# ArduinoShield101.net
KiCad netlist of a schematic drawn in EAGLE
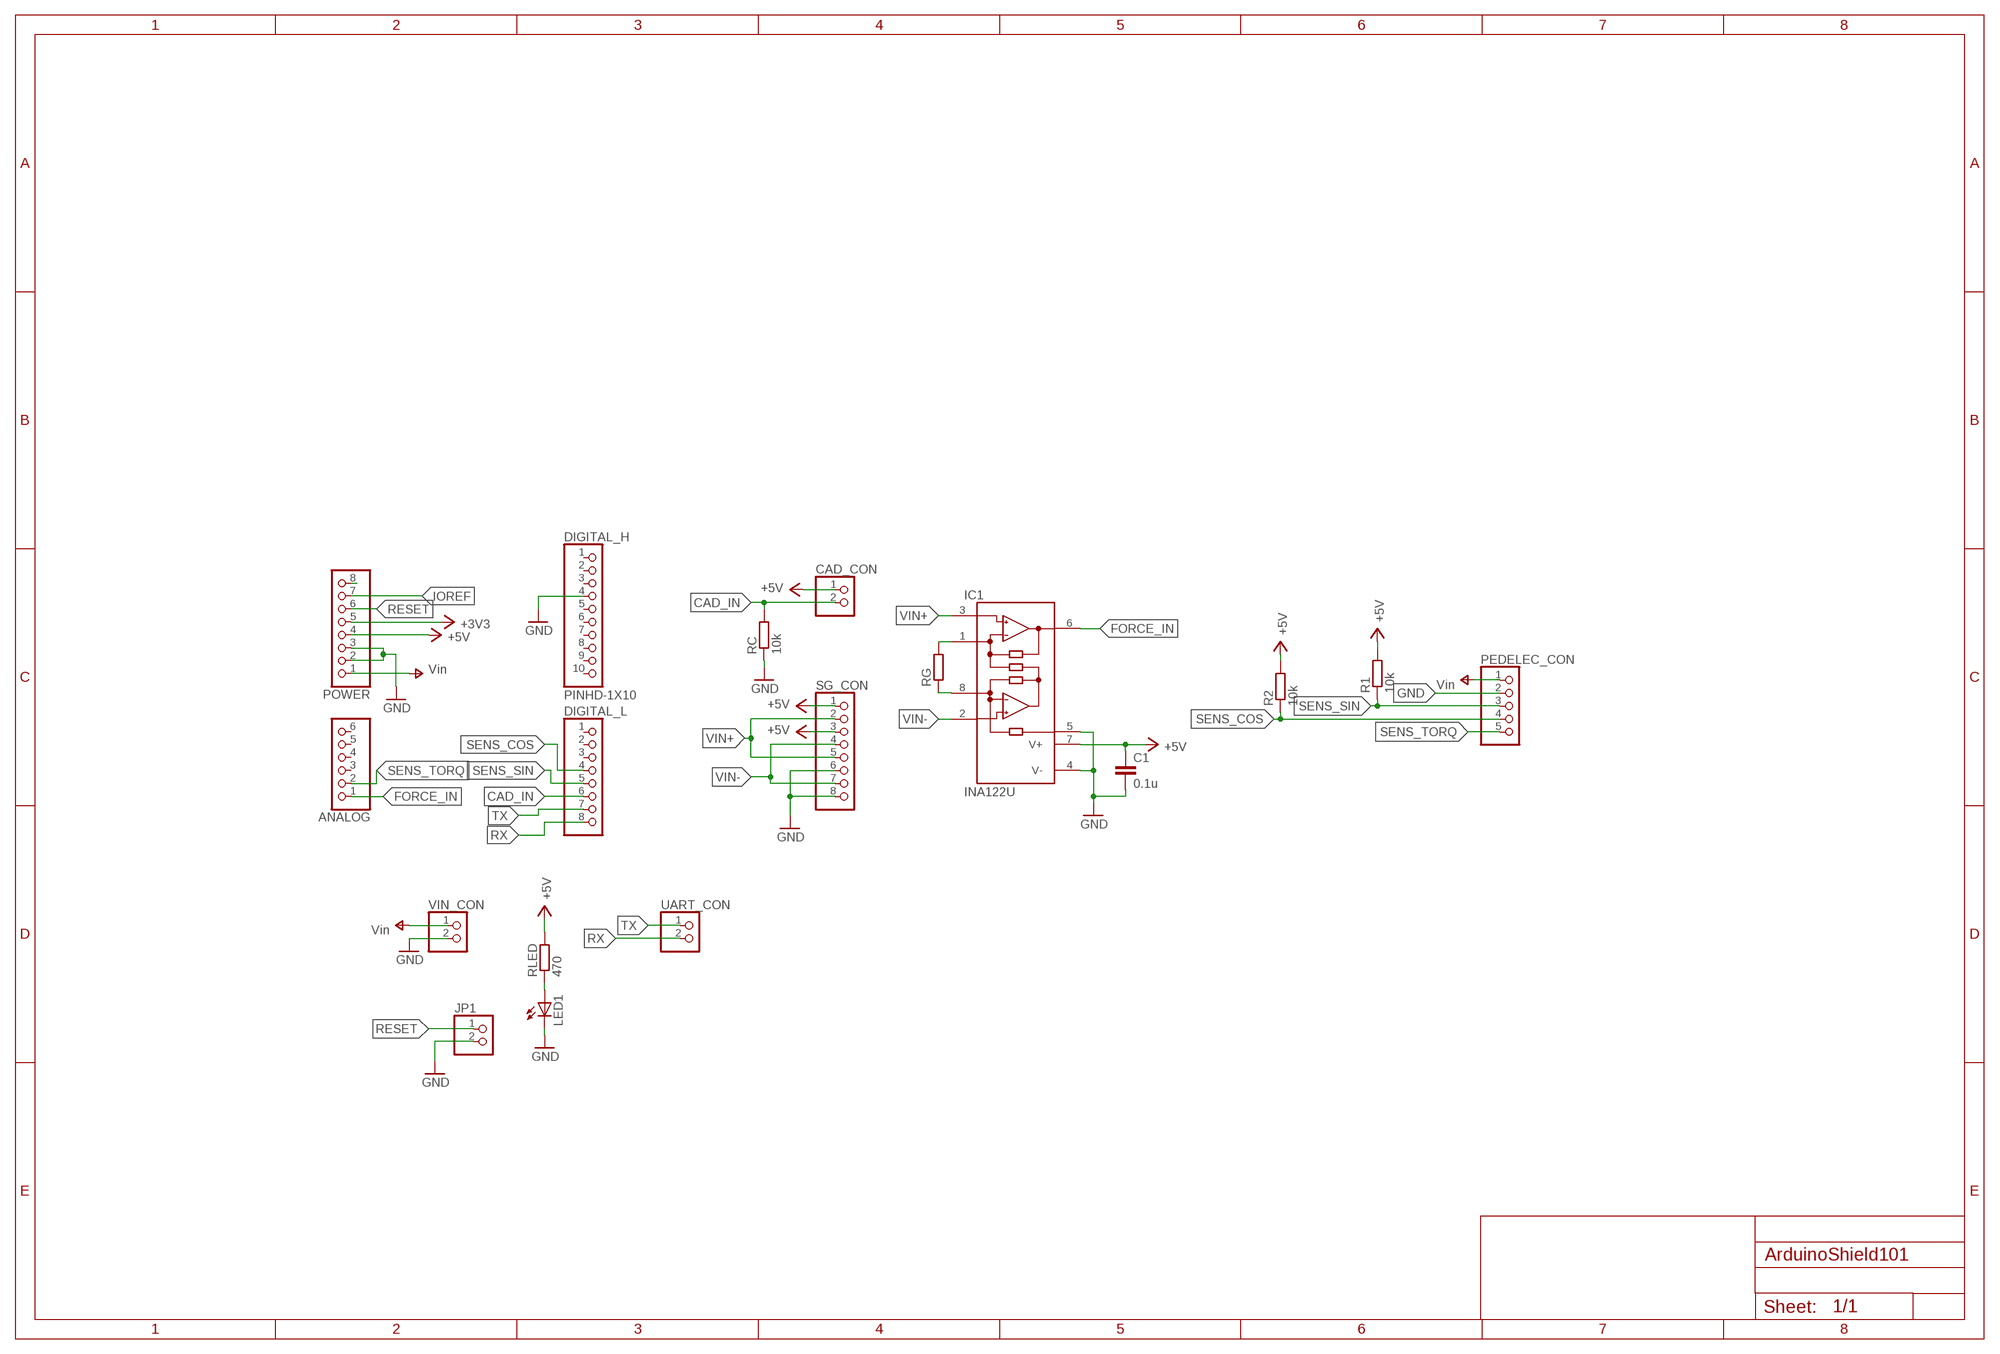
[diagram p0: schematic, sheet 1]

(export (version "E")
  (design (tool "Eeschema 10.0.6"))
  (components
    (comp (ref "ANALOG")
      (value "PINHD-1X6B")
      (footprint "eagle-import:1X06-BIG")
      (libsource (lib "eagle-import") (part "PINHD-1X6B"))
    )
    (comp (ref "C1")
      (value "0.1u")
      (footprint "eagle-import:C0603")
      (libsource (lib "eagle-import") (part "C-EUC0603"))
    )
    (comp (ref "CAD_CON")
      (value "PINHD-1X2/90")
      (footprint "eagle-import:1X02_90")
      (libsource (lib "eagle-import") (part "PINHD-1X2/90"))
    )
    (comp (ref "DIGITAL_H")
      (value "PINHD-1X10")
      (footprint "eagle-import:1X10-BIG")
      (libsource (lib "eagle-import") (part "PINHD-1X10"))
    )
    (comp (ref "DIGITAL_L")
      (value "PINHD-1X8BIG")
      (footprint "eagle-import:1X08-BIG")
      (libsource (lib "eagle-import") (part "PINHD-1X8BIG"))
    )
    (comp (ref "IC1")
      (value "INA122U")
      (footprint "eagle-import:SO08")
      (libsource (lib "eagle-import") (part "INA122U"))
    )
    (comp (ref "JP1")
      (value "PINHD-1X2")
      (footprint "eagle-import:1X02")
      (libsource (lib "eagle-import") (part "PINHD-1X2"))
    )
    (comp (ref "LED1")
      (value "LEDCHIPLED_0603")
      (footprint "eagle-import:CHIPLED_0603")
      (libsource (lib "eagle-import") (part "LEDCHIPLED_0603"))
    )
    (comp (ref "PEDELEC_CON")
      (value "PINHD-1X5/90")
      (footprint "eagle-import:1X05_90")
      (libsource (lib "eagle-import") (part "PINHD-1X5/90"))
    )
    (comp (ref "POWER")
      (value "PINHD-1X8BIG")
      (footprint "eagle-import:1X08-BIG")
      (libsource (lib "eagle-import") (part "PINHD-1X8BIG"))
    )
    (comp (ref "R1")
      (value "10k")
      (footprint "eagle-import:R0603")
      (libsource (lib "eagle-import") (part "R-EU_R0603"))
    )
    (comp (ref "R2")
      (value "10k")
      (footprint "eagle-import:R0603")
      (libsource (lib "eagle-import") (part "R-EU_R0603"))
    )
    (comp (ref "RC")
      (value "10k")
      (footprint "eagle-import:R0603")
      (libsource (lib "eagle-import") (part "R-EU_R0603"))
    )
    (comp (ref "RG")
      (value "R-EU_R0603")
      (footprint "eagle-import:R0603")
      (libsource (lib "eagle-import") (part "R-EU_R0603"))
    )
    (comp (ref "RLED")
      (value "470")
      (footprint "eagle-import:R0603")
      (libsource (lib "eagle-import") (part "R-EU_R0603"))
    )
    (comp (ref "SG_CON")
      (value "PINHD-1X8/90")
      (footprint "eagle-import:1X08_90")
      (libsource (lib "eagle-import") (part "PINHD-1X8/90"))
    )
    (comp (ref "UART_CON")
      (value "PINHD-1X2/90")
      (footprint "eagle-import:1X02_90")
      (libsource (lib "eagle-import") (part "PINHD-1X2/90"))
    )
    (comp (ref "VIN_CON")
      (value "PINHD-1X2/90")
      (footprint "eagle-import:1X02_90")
      (libsource (lib "eagle-import") (part "PINHD-1X2/90"))
    )
  )
  (nets
    (net (code "1") (name "+3V3") (class "Default")
      (node (ref "POWER") (pin "5") (pinfunction "5_5") (pintype "passive"))
    )
    (net (code "2") (name "+5V") (class "Default")
      (node (ref "C1") (pin "1") (pinfunction "1_1") (pintype "passive"))
      (node (ref "CAD_CON") (pin "1") (pinfunction "1_1") (pintype "passive"))
      (node (ref "IC1") (pin "7") (pinfunction "V+_7") (pintype "power_in"))
      (node (ref "POWER") (pin "4") (pinfunction "4_4") (pintype "passive"))
      (node (ref "R1") (pin "2") (pinfunction "2_2") (pintype "passive"))
      (node (ref "R2") (pin "2") (pinfunction "2_2") (pintype "passive"))
      (node (ref "RLED") (pin "2") (pinfunction "2_2") (pintype "passive"))
      (node (ref "SG_CON") (pin "1") (pinfunction "1_1") (pintype "passive"))
      (node (ref "SG_CON") (pin "3") (pinfunction "3_3") (pintype "passive"))
    )
    (net (code "3") (name "CAD_IN") (class "Default")
      (node (ref "CAD_CON") (pin "2") (pinfunction "2_2") (pintype "passive"))
      (node (ref "DIGITAL_L") (pin "6") (pinfunction "6_6") (pintype "passive"))
      (node (ref "RC") (pin "2") (pinfunction "2_2") (pintype "passive"))
    )
    (net (code "4") (name "FORCE_IN") (class "Default")
      (node (ref "ANALOG") (pin "1") (pinfunction "1_1") (pintype "passive"))
      (node (ref "IC1") (pin "6") (pinfunction "OUT_6") (pintype "output"))
    )
    (net (code "5") (name "GND") (class "Default")
      (node (ref "C1") (pin "2") (pinfunction "2_2") (pintype "passive"))
      (node (ref "DIGITAL_H") (pin "4") (pinfunction "4_4") (pintype "passive"))
      (node (ref "IC1") (pin "4") (pinfunction "V-_4") (pintype "power_in"))
      (node (ref "IC1") (pin "5") (pinfunction "REF_5") (pintype "passive"))
      (node (ref "JP1") (pin "2") (pinfunction "2_2") (pintype "passive"))
      (node (ref "LED1") (pin "C") (pinfunction "C_C") (pintype "passive"))
      (node (ref "PEDELEC_CON") (pin "2") (pinfunction "2_2") (pintype "passive"))
      (node (ref "POWER") (pin "2") (pinfunction "2_2") (pintype "passive"))
      (node (ref "POWER") (pin "3") (pinfunction "3_3") (pintype "passive"))
      (node (ref "RC") (pin "1") (pinfunction "1_1") (pintype "passive"))
      (node (ref "SG_CON") (pin "6") (pinfunction "6_6") (pintype "passive"))
      (node (ref "SG_CON") (pin "8") (pinfunction "8_8") (pintype "passive"))
      (node (ref "VIN_CON") (pin "2") (pinfunction "2_2") (pintype "passive"))
    )
    (net (code "6") (name "IOREF") (class "Default")
      (node (ref "POWER") (pin "7") (pinfunction "7_7") (pintype "passive"))
    )
    (net (code "7") (name "Net-(IC1-RG-Pad1)") (class "Default")
      (node (ref "IC1") (pin "1") (pinfunction "RG_1") (pintype "passive"))
      (node (ref "RG") (pin "2") (pinfunction "2_2") (pintype "passive"))
    )
    (net (code "8") (name "Net-(IC1-RG-Pad8)") (class "Default")
      (node (ref "IC1") (pin "8") (pinfunction "RG_8") (pintype "passive"))
      (node (ref "RG") (pin "1") (pinfunction "1_1") (pintype "passive"))
    )
    (net (code "9") (name "Net-(LED1-PadA)") (class "Default")
      (node (ref "LED1") (pin "A") (pinfunction "A_A") (pintype "passive"))
      (node (ref "RLED") (pin "1") (pinfunction "1_1") (pintype "passive"))
    )
    (net (code "10") (name "RESET") (class "Default")
      (node (ref "JP1") (pin "1") (pinfunction "1_1") (pintype "passive"))
      (node (ref "POWER") (pin "6") (pinfunction "6_6") (pintype "passive"))
    )
    (net (code "11") (name "RX") (class "Default")
      (node (ref "DIGITAL_L") (pin "8") (pinfunction "8_8") (pintype "passive"))
      (node (ref "UART_CON") (pin "2") (pinfunction "2_2") (pintype "passive"))
    )
    (net (code "12") (name "SENS_COS") (class "Default")
      (node (ref "DIGITAL_L") (pin "4") (pinfunction "4_4") (pintype "passive"))
      (node (ref "PEDELEC_CON") (pin "4") (pinfunction "4_4") (pintype "passive"))
      (node (ref "R2") (pin "1") (pinfunction "1_1") (pintype "passive"))
    )
    (net (code "13") (name "SENS_SIN") (class "Default")
      (node (ref "DIGITAL_L") (pin "5") (pinfunction "5_5") (pintype "passive"))
      (node (ref "PEDELEC_CON") (pin "3") (pinfunction "3_3") (pintype "passive"))
      (node (ref "R1") (pin "1") (pinfunction "1_1") (pintype "passive"))
    )
    (net (code "14") (name "SENS_TORQ") (class "Default")
      (node (ref "ANALOG") (pin "2") (pinfunction "2_2") (pintype "passive"))
      (node (ref "PEDELEC_CON") (pin "5") (pinfunction "5_5") (pintype "passive"))
    )
    (net (code "15") (name "TX") (class "Default")
      (node (ref "DIGITAL_L") (pin "7") (pinfunction "7_7") (pintype "passive"))
      (node (ref "UART_CON") (pin "1") (pinfunction "1_1") (pintype "passive"))
    )
    (net (code "16") (name "VIN+") (class "Default")
      (node (ref "IC1") (pin "3") (pinfunction "+IN_3") (pintype "input"))
      (node (ref "SG_CON") (pin "2") (pinfunction "2_2") (pintype "passive"))
      (node (ref "SG_CON") (pin "5") (pinfunction "5_5") (pintype "passive"))
    )
    (net (code "17") (name "VIN-") (class "Default")
      (node (ref "IC1") (pin "2") (pinfunction "-IN_2") (pintype "input"))
      (node (ref "SG_CON") (pin "4") (pinfunction "4_4") (pintype "passive"))
      (node (ref "SG_CON") (pin "7") (pinfunction "7_7") (pintype "passive"))
    )
    (net (code "18") (name "Vin") (class "Default")
      (node (ref "PEDELEC_CON") (pin "1") (pinfunction "1_1") (pintype "passive"))
      (node (ref "POWER") (pin "1") (pinfunction "1_1") (pintype "passive"))
      (node (ref "VIN_CON") (pin "1") (pinfunction "1_1") (pintype "passive"))
    )
    (net (code "19") (name "unconnected-(ANALOG-Pad3)") (class "Default")
      (node (ref "ANALOG") (pin "3") (pinfunction "3_3") (pintype "passive"))
    )
    (net (code "20") (name "unconnected-(ANALOG-Pad4)") (class "Default")
      (node (ref "ANALOG") (pin "4") (pinfunction "4_4") (pintype "passive"))
    )
    (net (code "21") (name "unconnected-(ANALOG-Pad5)") (class "Default")
      (node (ref "ANALOG") (pin "5") (pinfunction "5_5") (pintype "passive"))
    )
    (net (code "22") (name "unconnected-(ANALOG-Pad6)") (class "Default")
      (node (ref "ANALOG") (pin "6") (pinfunction "6_6") (pintype "passive"))
    )
    (net (code "23") (name "unconnected-(DIGITAL_H-Pad1)") (class "Default")
      (node (ref "DIGITAL_H") (pin "1") (pinfunction "1_1") (pintype "passive"))
    )
    (net (code "24") (name "unconnected-(DIGITAL_H-Pad2)") (class "Default")
      (node (ref "DIGITAL_H") (pin "2") (pinfunction "2_2") (pintype "passive"))
    )
    (net (code "25") (name "unconnected-(DIGITAL_H-Pad3)") (class "Default")
      (node (ref "DIGITAL_H") (pin "3") (pinfunction "3_3") (pintype "passive"))
    )
    (net (code "26") (name "unconnected-(DIGITAL_H-Pad5)") (class "Default")
      (node (ref "DIGITAL_H") (pin "5") (pinfunction "5_5") (pintype "passive"))
    )
    (net (code "27") (name "unconnected-(DIGITAL_H-Pad6)") (class "Default")
      (node (ref "DIGITAL_H") (pin "6") (pinfunction "6_6") (pintype "passive"))
    )
    (net (code "28") (name "unconnected-(DIGITAL_H-Pad7)") (class "Default")
      (node (ref "DIGITAL_H") (pin "7") (pinfunction "7_7") (pintype "passive"))
    )
    (net (code "29") (name "unconnected-(DIGITAL_H-Pad8)") (class "Default")
      (node (ref "DIGITAL_H") (pin "8") (pinfunction "8_8") (pintype "passive"))
    )
    (net (code "30") (name "unconnected-(DIGITAL_H-Pad9)") (class "Default")
      (node (ref "DIGITAL_H") (pin "9") (pinfunction "9_9") (pintype "passive"))
    )
    (net (code "31") (name "unconnected-(DIGITAL_H-Pad10)") (class "Default")
      (node (ref "DIGITAL_H") (pin "10") (pinfunction "10_10") (pintype "passive"))
    )
    (net (code "32") (name "unconnected-(DIGITAL_L-Pad1)") (class "Default")
      (node (ref "DIGITAL_L") (pin "1") (pinfunction "1_1") (pintype "passive"))
    )
    (net (code "33") (name "unconnected-(DIGITAL_L-Pad2)") (class "Default")
      (node (ref "DIGITAL_L") (pin "2") (pinfunction "2_2") (pintype "passive"))
    )
    (net (code "34") (name "unconnected-(DIGITAL_L-Pad3)") (class "Default")
      (node (ref "DIGITAL_L") (pin "3") (pinfunction "3_3") (pintype "passive"))
    )
    (net (code "35") (name "unconnected-(POWER-Pad8)") (class "Default")
      (node (ref "POWER") (pin "8") (pinfunction "8_8") (pintype "passive"))
    )
  )
)
